# Hedgehog.net
KiCad netlist of a schematic drawn in EasyEDA Pro
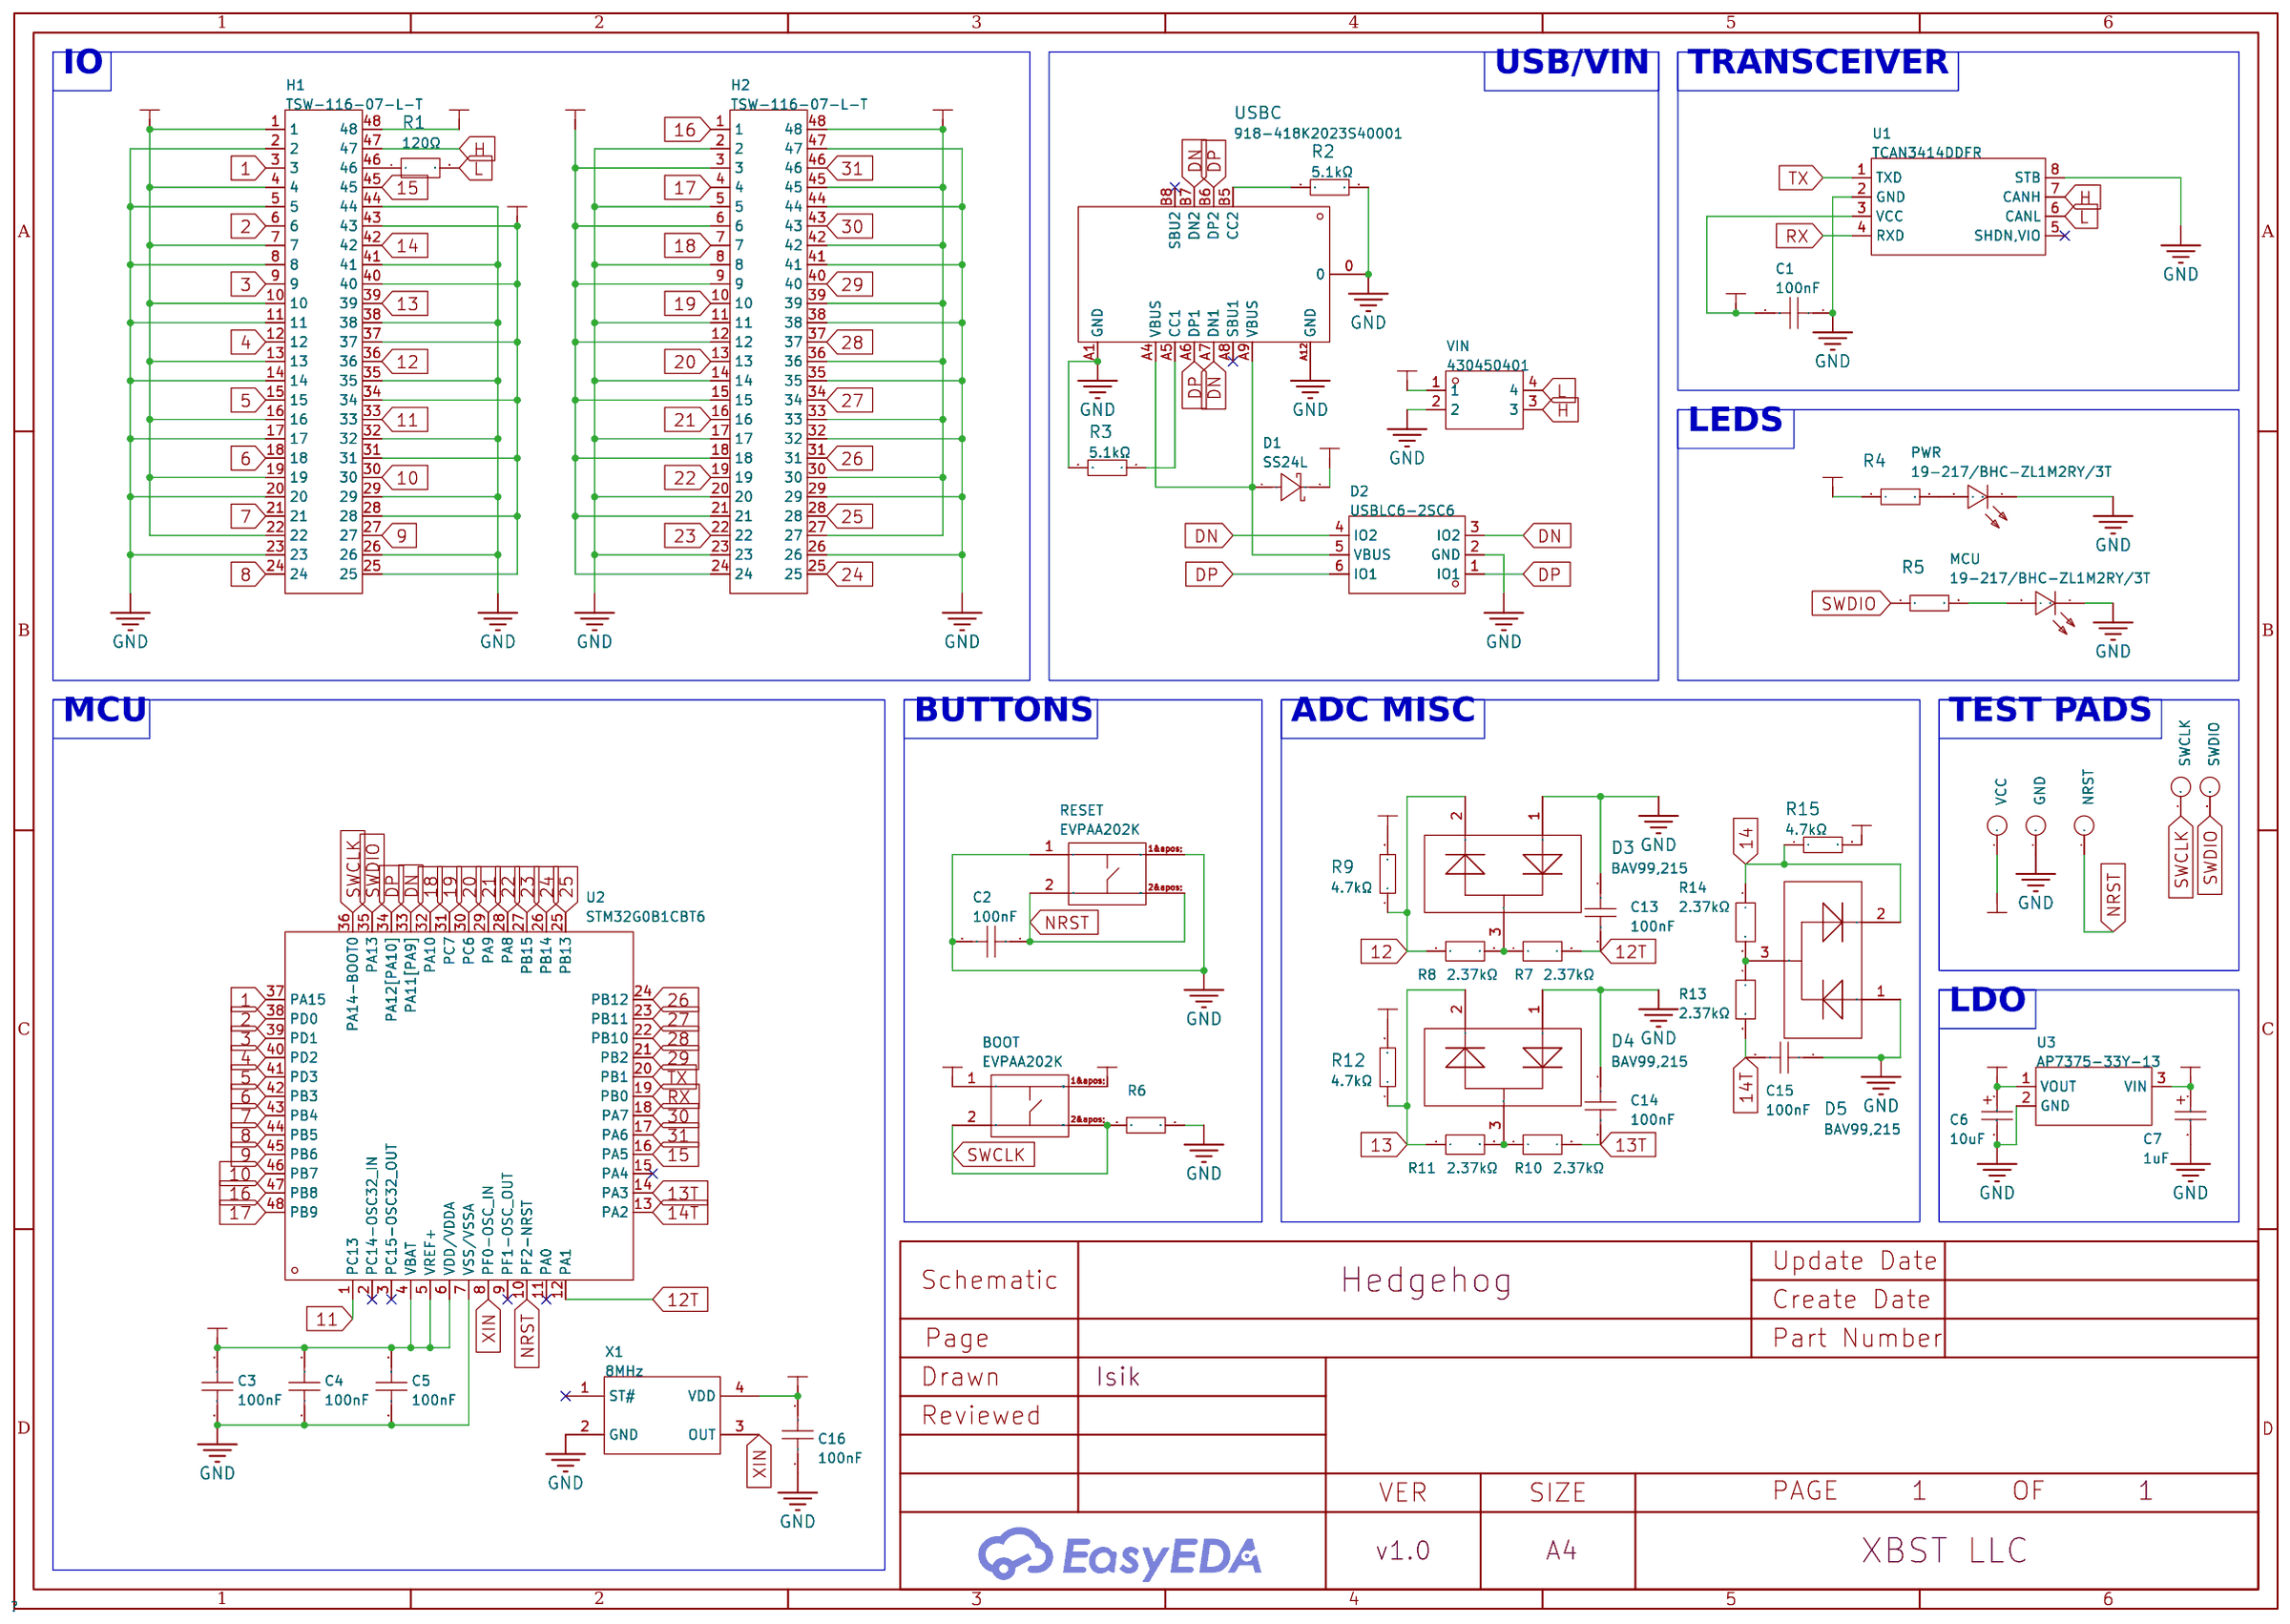
[diagram p0: schematic sheet]

(export (version "E")
  (design (tool "Eeschema 10.0.6"))
  (components
    (comp (ref "BOOT")
      (value "EVPAA202K")
      (footprint "easyedapro:KEY-SMD_4P-L3.5-W2.9-P1.48-LS4.3-TL")
      (fields (field (name "Manufacturer") "PANASONIC(松下)"))
      (libsource (lib "easyedapro") (part "EVPAA202K"))
    )
    (comp (ref "C1")
      (value "100nF")
      (footprint "easyedapro:C0402")
      (fields
        (field (name "Manufacturer Part") "CL05B104KB54PNC")
        (field (name "Manufacturer") "SAMSUNG(三星)")
      )
      (libsource (lib "easyedapro") (part "CL05B104KB54PNC"))
    )
    (comp (ref "C2")
      (value "100nF")
      (footprint "easyedapro:C0402")
      (fields
        (field (name "Manufacturer Part") "CL05B104KB54PNC")
        (field (name "Manufacturer") "SAMSUNG(三星)")
      )
      (libsource (lib "easyedapro") (part "CL05B104KB54PNC"))
    )
    (comp (ref "C3")
      (value "100nF")
      (footprint "easyedapro:C0402")
      (fields
        (field (name "Manufacturer Part") "CL05B104KB54PNC")
        (field (name "Manufacturer") "SAMSUNG(三星)")
      )
      (libsource (lib "easyedapro") (part "CL05B104KB54PNC"))
    )
    (comp (ref "C4")
      (value "100nF")
      (footprint "easyedapro:C0402")
      (fields
        (field (name "Manufacturer Part") "CL05B104KB54PNC")
        (field (name "Manufacturer") "SAMSUNG(三星)")
      )
      (libsource (lib "easyedapro") (part "CL05B104KB54PNC"))
    )
    (comp (ref "C5")
      (value "100nF")
      (footprint "easyedapro:C0402")
      (fields
        (field (name "Manufacturer Part") "CL05B104KB54PNC")
        (field (name "Manufacturer") "SAMSUNG(三星)")
      )
      (libsource (lib "easyedapro") (part "CL05B104KB54PNC"))
    )
    (comp (ref "C6")
      (value "10uF")
      (footprint "easyedapro:CAP-SMD_L3.2-W1.6-RD-C7171")
      (fields (field (name "Manufacturer Part") "TAJA106K016RNJ") (field (name "Manufacturer") "Kyocera AVX"))
      (libsource (lib "easyedapro") (part "TAJA106K016RNJ"))
    )
    (comp (ref "C7")
      (value "1uF")
      (footprint "easyedapro:CAP-SMD_L3.2-W1.6-RD-C7171")
      (fields (field (name "Manufacturer Part") "TAJA105K035RNJ") (field (name "Manufacturer") "Kyocera AVX"))
      (libsource (lib "easyedapro") (part "TAJA106K016RNJ"))
    )
    (comp (ref "C13")
      (value "100nF")
      (footprint "easyedapro:C0402")
      (fields
        (field (name "Manufacturer Part") "CL05B104KB54PNC")
        (field (name "Manufacturer") "SAMSUNG(三星)")
      )
      (libsource (lib "easyedapro") (part "CL05B104KB54PNC"))
    )
    (comp (ref "C14")
      (value "100nF")
      (footprint "easyedapro:C0402")
      (fields
        (field (name "Manufacturer Part") "CL05B104KB54PNC")
        (field (name "Manufacturer") "SAMSUNG(三星)")
      )
      (libsource (lib "easyedapro") (part "CL05B104KB54PNC"))
    )
    (comp (ref "C15")
      (value "100nF")
      (footprint "easyedapro:C0402")
      (fields
        (field (name "Manufacturer Part") "CL05B104KB54PNC")
        (field (name "Manufacturer") "SAMSUNG(三星)")
      )
      (libsource (lib "easyedapro") (part "CL05B104KB54PNC"))
    )
    (comp (ref "C16")
      (value "100nF")
      (footprint "easyedapro:C0402")
      (fields
        (field (name "Manufacturer Part") "CL05B104KB54PNC")
        (field (name "Manufacturer") "SAMSUNG(三星)")
      )
      (libsource (lib "easyedapro") (part "CL05B104KB54PNC"))
    )
    (comp (ref "D1")
      (value "SS24L")
      (footprint "easyedapro:SOD-123FL_L2.8-W1.8-LS3.7-R-RD")
      (fields (field (name "Manufacturer") "Hottech(合科泰)"))
      (libsource (lib "easyedapro") (part "SS24L"))
    )
    (comp (ref "D2")
      (value "USBLC6-2SC6")
      (footprint "easyedapro:SOT-23-6_L2.9-W1.6-P0.95-LS2.8-BL")
      (fields (field (name "Manufacturer") "TECH PUBLIC(台舟)"))
      (libsource (lib "easyedapro") (part "USBLC6-2SC6_C2827654"))
    )
    (comp (ref "D3")
      (value "BAV99,215")
      (footprint "easyedapro:SOT-23-3_L2.9-W1.6-P1.90-LS2.8-BR")
      (fields (field (name "Manufacturer") "Nexperia(安世)"))
      (libsource (lib "easyedapro") (part "BAV99,215"))
    )
    (comp (ref "D4")
      (value "BAV99,215")
      (footprint "easyedapro:SOT-23-3_L2.9-W1.6-P1.90-LS2.8-BR")
      (fields (field (name "Manufacturer") "Nexperia(安世)"))
      (libsource (lib "easyedapro") (part "BAV99,215"))
    )
    (comp (ref "D5")
      (value "BAV99,215")
      (footprint "easyedapro:SOT-23-3_L2.9-W1.6-P1.90-LS2.8-BR")
      (fields (field (name "Manufacturer") "Nexperia(安世)"))
      (libsource (lib "easyedapro") (part "BAV99,215"))
    )
    (comp (ref "GND") (value "NO") (footprint "easyedapro:TP") (libsource (lib "easyedapro") (part "NO")))
    (comp (ref "H1")
      (value "TSW-116-07-L-T")
      (footprint "easyedapro:HDR-TH_48P-P2.54-V-M-R3-C16-S2.54_1")
      (fields (field (name "Manufacturer") "SAMTEC"))
      (libsource (lib "easyedapro") (part "TSW-116-07-L-T"))
    )
    (comp (ref "H2")
      (value "TSW-116-07-L-T")
      (footprint "easyedapro:HDR-TH_48P-P2.54-V-M-R3-C16-S2.54_1")
      (fields (field (name "Manufacturer") "SAMTEC"))
      (libsource (lib "easyedapro") (part "TSW-116-07-L-T"))
    )
    (comp (ref "MCU")
      (value "19-217/BHC-ZL1M2RY/3T")
      (footprint "easyedapro:LED0603-FD_BLUE")
      (fields (field (name "Manufacturer") "EVERLIGHT(亿光)"))
      (libsource (lib "easyedapro") (part "19-217/BHC-ZL1M2RY/3T"))
    )
    (comp (ref "NRST") (value "NO") (footprint "easyedapro:TP") (libsource (lib "easyedapro") (part "NO")))
    (comp (ref "PWR")
      (value "19-217/BHC-ZL1M2RY/3T")
      (footprint "easyedapro:LED0603-FD_BLUE")
      (fields (field (name "Manufacturer") "EVERLIGHT(亿光)"))
      (libsource (lib "easyedapro") (part "19-217/BHC-ZL1M2RY/3T"))
    )
    (comp (ref "R1")
      (value "120Ω")
      (footprint "easyedapro:R0805")
      (fields (field (name "Manufacturer Part") "ERJP06F1200V") (field (name "Manufacturer") "PANASONIC(松下)"))
      (libsource (lib "easyedapro") (part "ERJP06F1200V"))
    )
    (comp (ref "R2")
      (value "5.1kΩ")
      (footprint "easyedapro:R0402")
      (fields
        (field (name "Manufacturer Part") "0402WGF5101TCE")
        (field (name "Manufacturer") "UNI-ROYAL(厚声)")
      )
      (libsource (lib "easyedapro") (part "0402WGF5101TCE"))
    )
    (comp (ref "R3")
      (value "5.1kΩ")
      (footprint "easyedapro:R0402")
      (fields
        (field (name "Manufacturer Part") "0402WGF5101TCE")
        (field (name "Manufacturer") "UNI-ROYAL(厚声)")
      )
      (libsource (lib "easyedapro") (part "0402WGF5101TCE"))
    )
    (comp (ref "R4")
      (value "1.5kΩ")
      (footprint "easyedapro:R0402")
      (fields
        (field (name "Manufacturer Part") "0402WGF1501TCE")
        (field (name "Manufacturer") "UNI-ROYAL(厚声)")
      )
      (libsource (lib "easyedapro") (part "0402WGF1501TCE"))
    )
    (comp (ref "R5")
      (value "1.5kΩ")
      (footprint "easyedapro:R0402")
      (fields
        (field (name "Manufacturer Part") "0402WGF1501TCE")
        (field (name "Manufacturer") "UNI-ROYAL(厚声)")
      )
      (libsource (lib "easyedapro") (part "0402WGF1501TCE"))
    )
    (comp (ref "R6")
      (value "10kΩ")
      (footprint "easyedapro:R0402")
      (fields
        (field (name "Manufacturer Part") "0402WGF1002TCE")
        (field (name "Manufacturer") "UNI-ROYAL(厚声)")
      )
      (libsource (lib "easyedapro") (part "0402WGF1002TCE"))
    )
    (comp (ref "R7")
      (value "2.37kΩ")
      (footprint "easyedapro:R0402")
      (fields (field (name "Manufacturer Part") "RC0402FR-072K37L") (field (name "Manufacturer") "YAGEO(国巨)"))
      (libsource (lib "easyedapro") (part "RC0402FR-072K37L_C294439"))
    )
    (comp (ref "R8")
      (value "2.37kΩ")
      (footprint "easyedapro:R0402")
      (fields (field (name "Manufacturer Part") "RC0402FR-072K37L") (field (name "Manufacturer") "YAGEO(国巨)"))
      (libsource (lib "easyedapro") (part "RC0402FR-072K37L_C294439"))
    )
    (comp (ref "R9")
      (value "4.7kΩ")
      (footprint "easyedapro:R0402")
      (fields
        (field (name "Manufacturer Part") "0402WGF4701TCE")
        (field (name "Manufacturer") "UNI-ROYAL(厚声)")
      )
      (libsource (lib "easyedapro") (part "0402WGF4701TCE"))
    )
    (comp (ref "R10")
      (value "2.37kΩ")
      (footprint "easyedapro:R0402")
      (fields (field (name "Manufacturer Part") "RC0402FR-072K37L") (field (name "Manufacturer") "YAGEO(国巨)"))
      (libsource (lib "easyedapro") (part "RC0402FR-072K37L_C294439"))
    )
    (comp (ref "R11")
      (value "2.37kΩ")
      (footprint "easyedapro:R0402")
      (fields (field (name "Manufacturer Part") "RC0402FR-072K37L") (field (name "Manufacturer") "YAGEO(国巨)"))
      (libsource (lib "easyedapro") (part "RC0402FR-072K37L_C294439"))
    )
    (comp (ref "R12")
      (value "4.7kΩ")
      (footprint "easyedapro:R0402")
      (fields
        (field (name "Manufacturer Part") "0402WGF4701TCE")
        (field (name "Manufacturer") "UNI-ROYAL(厚声)")
      )
      (libsource (lib "easyedapro") (part "0402WGF4701TCE"))
    )
    (comp (ref "R13")
      (value "2.37kΩ")
      (footprint "easyedapro:R0402")
      (fields (field (name "Manufacturer Part") "RC0402FR-072K37L") (field (name "Manufacturer") "YAGEO(国巨)"))
      (libsource (lib "easyedapro") (part "RC0402FR-072K37L_C294439"))
    )
    (comp (ref "R14")
      (value "2.37kΩ")
      (footprint "easyedapro:R0402")
      (fields (field (name "Manufacturer Part") "RC0402FR-072K37L") (field (name "Manufacturer") "YAGEO(国巨)"))
      (libsource (lib "easyedapro") (part "RC0402FR-072K37L_C294439"))
    )
    (comp (ref "R15")
      (value "4.7kΩ")
      (footprint "easyedapro:R0402")
      (fields
        (field (name "Manufacturer Part") "0402WGF4701TCE")
        (field (name "Manufacturer") "UNI-ROYAL(厚声)")
      )
      (libsource (lib "easyedapro") (part "0402WGF4701TCE"))
    )
    (comp (ref "RESET")
      (value "EVPAA202K")
      (footprint "easyedapro:KEY-SMD_4P-L3.5-W2.9-P1.48-LS4.3-TL")
      (fields (field (name "Manufacturer") "PANASONIC(松下)"))
      (libsource (lib "easyedapro") (part "EVPAA202K"))
    )
    (comp (ref "SWCLK") (value "NO") (footprint "easyedapro:TP") (libsource (lib "easyedapro") (part "NO")))
    (comp (ref "SWDIO") (value "NO") (footprint "easyedapro:TP") (libsource (lib "easyedapro") (part "NO")))
    (comp (ref "U1")
      (value "TCAN3414DDFR")
      (footprint "easyedapro:TSOT-23-8_L2.9-W1.6-P0.65-LS2.8-BR")
      (fields (field (name "Manufacturer") "TI(德州仪器)"))
      (libsource (lib "easyedapro") (part "TCAN3414DDFR"))
    )
    (comp (ref "U2")
      (value "STM32G0B1CBT6")
      (footprint "easyedapro:LQFP-48_L7.0-W7.0-P0.50-LS9.0-BL")
      (fields (field (name "Manufacturer") "ST(意法半导体)"))
      (libsource (lib "easyedapro") (part "STM32G0B1CBT6"))
    )
    (comp (ref "U3")
      (value "AP7375-33Y-13")
      (footprint "easyedapro:SOT-89-3_L4.5-W2.5-P1.50-LS4.0-BR")
      (fields (field (name "Manufacturer") "DIODES(美台)"))
      (libsource (lib "easyedapro") (part "AP7375-33Y-13"))
    )
    (comp (ref "USBC")
      (value "918-418K2023S40001")
      (footprint "easyedapro:USB-C-SMD_TYPE-C-USB-17")
      (fields (field (name "Manufacturer") "精拓金"))
      (libsource (lib "easyedapro") (part "USB3.1C16PFSMT"))
    )
    (comp (ref "VCC") (value "NO") (footprint "easyedapro:TP") (libsource (lib "easyedapro") (part "NO")))
    (comp (ref "VIN")
      (value "430450401")
      (footprint "easyedapro:CONN-TH_0430450400")
      (fields (field (name "Manufacturer") "MOLEX"))
      (libsource (lib "easyedapro") (part "430450401"))
    )
    (comp (ref "X1")
      (value "8MHz")
      (footprint "easyedapro:OSC-SMD_4P-L2.5-W2.0-BL")
      (fields (field (name "Manufacturer Part") "SG-210STF 8.0000ML0") (field (name "Manufacturer") "EPSON"))
      (libsource (lib "easyedapro") (part "X1G004171003300"))
    )
  )
  (nets
    (net (code "1") (name "1") (class "Default")
      (node (ref "H1") (pin "3") (pinfunction "3_3") (pintype "unspecified"))
      (node (ref "U2") (pin "37") (pinfunction "PA15_37") (pintype "unspecified"))
    )
    (net (code "2") (name "2") (class "Default")
      (node (ref "H1") (pin "6") (pinfunction "6_6") (pintype "unspecified"))
      (node (ref "U2") (pin "38") (pinfunction "PD0_38") (pintype "unspecified"))
    )
    (net (code "3") (name "3") (class "Default")
      (node (ref "H1") (pin "9") (pinfunction "9_9") (pintype "unspecified"))
      (node (ref "U2") (pin "39") (pinfunction "PD1_39") (pintype "unspecified"))
    )
    (net (code "4") (name "3V3") (class "Default")
      (node (ref "BOOT") (pin "1") (pinfunction "1_1") (pintype "unspecified"))
      (node (ref "BOOT") (pin "1&apos;") (pinfunction "1&apos;_1&apos;") (pintype "unspecified"))
      (node (ref "C1") (pin "2") (pinfunction "2_2") (pintype "input"))
      (node (ref "C16") (pin "2") (pinfunction "2_2") (pintype "input"))
      (node (ref "C3") (pin "1") (pinfunction "1_1") (pintype "input"))
      (node (ref "C4") (pin "2") (pinfunction "2_2") (pintype "input"))
      (node (ref "C5") (pin "2") (pinfunction "2_2") (pintype "input"))
      (node (ref "C6") (pin "1") (pinfunction "1_1") (pintype "input"))
      (node (ref "H1") (pin "1") (pinfunction "1_1") (pintype "unspecified"))
      (node (ref "H1") (pin "10") (pinfunction "10_10") (pintype "unspecified"))
      (node (ref "H1") (pin "13") (pinfunction "13_13") (pintype "unspecified"))
      (node (ref "H1") (pin "16") (pinfunction "16_16") (pintype "unspecified"))
      (node (ref "H1") (pin "19") (pinfunction "19_19") (pintype "unspecified"))
      (node (ref "H1") (pin "22") (pinfunction "22_22") (pintype "unspecified"))
      (node (ref "H1") (pin "25") (pinfunction "25_25") (pintype "unspecified"))
      (node (ref "H1") (pin "28") (pinfunction "28_28") (pintype "unspecified"))
      (node (ref "H1") (pin "31") (pinfunction "31_31") (pintype "unspecified"))
      (node (ref "H1") (pin "34") (pinfunction "34_34") (pintype "unspecified"))
      (node (ref "H1") (pin "37") (pinfunction "37_37") (pintype "unspecified"))
      (node (ref "H1") (pin "4") (pinfunction "4_4") (pintype "unspecified"))
      (node (ref "H1") (pin "40") (pinfunction "40_40") (pintype "unspecified"))
      (node (ref "H1") (pin "43") (pinfunction "43_43") (pintype "unspecified"))
      (node (ref "H1") (pin "7") (pinfunction "7_7") (pintype "unspecified"))
      (node (ref "H2") (pin "12") (pinfunction "12_12") (pintype "unspecified"))
      (node (ref "H2") (pin "15") (pinfunction "15_15") (pintype "unspecified"))
      (node (ref "H2") (pin "18") (pinfunction "18_18") (pintype "unspecified"))
      (node (ref "H2") (pin "21") (pinfunction "21_21") (pintype "unspecified"))
      (node (ref "H2") (pin "24") (pinfunction "24_24") (pintype "unspecified"))
      (node (ref "H2") (pin "27") (pinfunction "27_27") (pintype "unspecified"))
      (node (ref "H2") (pin "3") (pinfunction "3_3") (pintype "unspecified"))
      (node (ref "H2") (pin "30") (pinfunction "30_30") (pintype "unspecified"))
      (node (ref "H2") (pin "33") (pinfunction "33_33") (pintype "unspecified"))
      (node (ref "H2") (pin "36") (pinfunction "36_36") (pintype "unspecified"))
      (node (ref "H2") (pin "39") (pinfunction "39_39") (pintype "unspecified"))
      (node (ref "H2") (pin "42") (pinfunction "42_42") (pintype "unspecified"))
      (node (ref "H2") (pin "45") (pinfunction "45_45") (pintype "unspecified"))
      (node (ref "H2") (pin "48") (pinfunction "48_48") (pintype "unspecified"))
      (node (ref "H2") (pin "6") (pinfunction "6_6") (pintype "unspecified"))
      (node (ref "H2") (pin "9") (pinfunction "9_9") (pintype "unspecified"))
      (node (ref "R12") (pin "2") (pinfunction "2_2") (pintype "input"))
      (node (ref "R15") (pin "2") (pinfunction "2_2") (pintype "input"))
      (node (ref "R4") (pin "1") (pinfunction "1_1") (pintype "input"))
      (node (ref "R9") (pin "2") (pinfunction "2_2") (pintype "input"))
      (node (ref "U1") (pin "3") (pinfunction "VCC_3") (pintype "unspecified"))
      (node (ref "U2") (pin "4") (pinfunction "VBAT_4") (pintype "unspecified"))
      (node (ref "U2") (pin "5") (pinfunction "VREF+_5") (pintype "unspecified"))
      (node (ref "U2") (pin "6") (pinfunction "VDD/VDDA_6") (pintype "unspecified"))
      (node (ref "U3") (pin "1") (pinfunction "VOUT_1") (pintype "unspecified"))
      (node (ref "VCC") (pin "1") (pinfunction "1_1") (pintype "unspecified"))
      (node (ref "X1") (pin "4") (pinfunction "VDD_4") (pintype "unspecified"))
    )
    (net (code "5") (name "4") (class "Default")
      (node (ref "H1") (pin "12") (pinfunction "12_12") (pintype "unspecified"))
      (node (ref "U2") (pin "40") (pinfunction "PD2_40") (pintype "unspecified"))
    )
    (net (code "6") (name "5") (class "Default")
      (node (ref "H1") (pin "15") (pinfunction "15_15") (pintype "unspecified"))
      (node (ref "U2") (pin "41") (pinfunction "PD3_41") (pintype "unspecified"))
    )
    (net (code "7") (name "6") (class "Default")
      (node (ref "H1") (pin "18") (pinfunction "18_18") (pintype "unspecified"))
      (node (ref "U2") (pin "42") (pinfunction "PB3_42") (pintype "unspecified"))
    )
    (net (code "8") (name "7") (class "Default")
      (node (ref "H1") (pin "21") (pinfunction "21_21") (pintype "unspecified"))
      (node (ref "U2") (pin "43") (pinfunction "PB4_43") (pintype "unspecified"))
    )
    (net (code "9") (name "8") (class "Default")
      (node (ref "H1") (pin "24") (pinfunction "24_24") (pintype "unspecified"))
      (node (ref "U2") (pin "44") (pinfunction "PB5_44") (pintype "unspecified"))
    )
    (net (code "10") (name "9") (class "Default")
      (node (ref "H1") (pin "27") (pinfunction "27_27") (pintype "unspecified"))
      (node (ref "U2") (pin "45") (pinfunction "PB6_45") (pintype "unspecified"))
    )
    (net (code "11") (name "10") (class "Default")
      (node (ref "H1") (pin "30") (pinfunction "30_30") (pintype "unspecified"))
      (node (ref "U2") (pin "46") (pinfunction "PB7_46") (pintype "unspecified"))
    )
    (net (code "12") (name "11") (class "Default")
      (node (ref "H1") (pin "33") (pinfunction "33_33") (pintype "unspecified"))
      (node (ref "U2") (pin "1") (pinfunction "PC13_1") (pintype "unspecified"))
    )
    (net (code "13") (name "12") (class "Default")
      (node (ref "D3") (pin "2") (pinfunction "2_2") (pintype "input"))
      (node (ref "H1") (pin "36") (pinfunction "36_36") (pintype "unspecified"))
      (node (ref "R8") (pin "1") (pinfunction "1_1") (pintype "input"))
      (node (ref "R9") (pin "1") (pinfunction "1_1") (pintype "input"))
    )
    (net (code "14") (name "12T") (class "Default")
      (node (ref "C13") (pin "2") (pinfunction "2_2") (pintype "input"))
      (node (ref "R7") (pin "2") (pinfunction "2_2") (pintype "input"))
      (node (ref "U2") (pin "12") (pinfunction "PA1_12") (pintype "unspecified"))
    )
    (net (code "15") (name "13") (class "Default")
      (node (ref "D4") (pin "2") (pinfunction "2_2") (pintype "input"))
      (node (ref "H1") (pin "39") (pinfunction "39_39") (pintype "unspecified"))
      (node (ref "R11") (pin "1") (pinfunction "1_1") (pintype "input"))
      (node (ref "R12") (pin "1") (pinfunction "1_1") (pintype "input"))
    )
    (net (code "16") (name "13T") (class "Default")
      (node (ref "C14") (pin "2") (pinfunction "2_2") (pintype "input"))
      (node (ref "R10") (pin "2") (pinfunction "2_2") (pintype "input"))
      (node (ref "U2") (pin "14") (pinfunction "PA3_14") (pintype "unspecified"))
    )
    (net (code "17") (name "14") (class "Default")
      (node (ref "D5") (pin "2") (pinfunction "2_2") (pintype "input"))
      (node (ref "H1") (pin "42") (pinfunction "42_42") (pintype "unspecified"))
      (node (ref "R14") (pin "1") (pinfunction "1_1") (pintype "input"))
      (node (ref "R15") (pin "1") (pinfunction "1_1") (pintype "input"))
    )
    (net (code "18") (name "14T") (class "Default")
      (node (ref "C15") (pin "2") (pinfunction "2_2") (pintype "input"))
      (node (ref "R13") (pin "2") (pinfunction "2_2") (pintype "input"))
      (node (ref "U2") (pin "13") (pinfunction "PA2_13") (pintype "unspecified"))
    )
    (net (code "19") (name "15") (class "Default")
      (node (ref "H1") (pin "45") (pinfunction "45_45") (pintype "unspecified"))
      (node (ref "U2") (pin "16") (pinfunction "PA5_16") (pintype "unspecified"))
    )
    (net (code "20") (name "16") (class "Default")
      (node (ref "H2") (pin "1") (pinfunction "1_1") (pintype "unspecified"))
      (node (ref "U2") (pin "47") (pinfunction "PB8_47") (pintype "unspecified"))
    )
    (net (code "21") (name "17") (class "Default")
      (node (ref "H2") (pin "4") (pinfunction "4_4") (pintype "unspecified"))
      (node (ref "U2") (pin "48") (pinfunction "PB9_48") (pintype "unspecified"))
    )
    (net (code "22") (name "18") (class "Default")
      (node (ref "H2") (pin "7") (pinfunction "7_7") (pintype "unspecified"))
      (node (ref "U2") (pin "32") (pinfunction "PA10_32") (pintype "unspecified"))
    )
    (net (code "23") (name "19") (class "Default")
      (node (ref "H2") (pin "10") (pinfunction "10_10") (pintype "unspecified"))
      (node (ref "U2") (pin "31") (pinfunction "PC7_31") (pintype "unspecified"))
    )
    (net (code "24") (name "20") (class "Default")
      (node (ref "H2") (pin "13") (pinfunction "13_13") (pintype "unspecified"))
      (node (ref "U2") (pin "30") (pinfunction "PC6_30") (pintype "unspecified"))
    )
    (net (code "25") (name "21") (class "Default")
      (node (ref "H2") (pin "16") (pinfunction "16_16") (pintype "unspecified"))
      (node (ref "U2") (pin "29") (pinfunction "PA9_29") (pintype "unspecified"))
    )
    (net (code "26") (name "22") (class "Default")
      (node (ref "H2") (pin "19") (pinfunction "19_19") (pintype "unspecified"))
      (node (ref "U2") (pin "28") (pinfunction "PA8_28") (pintype "unspecified"))
    )
    (net (code "27") (name "23") (class "Default")
      (node (ref "H2") (pin "22") (pinfunction "22_22") (pintype "unspecified"))
      (node (ref "U2") (pin "27") (pinfunction "PB15_27") (pintype "unspecified"))
    )
    (net (code "28") (name "24") (class "Default")
      (node (ref "H2") (pin "25") (pinfunction "25_25") (pintype "unspecified"))
      (node (ref "U2") (pin "26") (pinfunction "PB14_26") (pintype "unspecified"))
    )
    (net (code "29") (name "25") (class "Default")
      (node (ref "H2") (pin "28") (pinfunction "28_28") (pintype "unspecified"))
      (node (ref "U2") (pin "25") (pinfunction "PB13_25") (pintype "unspecified"))
    )
    (net (code "30") (name "26") (class "Default")
      (node (ref "H2") (pin "31") (pinfunction "31_31") (pintype "unspecified"))
      (node (ref "U2") (pin "24") (pinfunction "PB12_24") (pintype "unspecified"))
    )
    (net (code "31") (name "27") (class "Default")
      (node (ref "H2") (pin "34") (pinfunction "34_34") (pintype "unspecified"))
      (node (ref "U2") (pin "23") (pinfunction "PB11_23") (pintype "unspecified"))
    )
    (net (code "32") (name "28") (class "Default")
      (node (ref "H2") (pin "37") (pinfunction "37_37") (pintype "unspecified"))
      (node (ref "U2") (pin "22") (pinfunction "PB10_22") (pintype "unspecified"))
    )
    (net (code "33") (name "29") (class "Default")
      (node (ref "H2") (pin "40") (pinfunction "40_40") (pintype "unspecified"))
      (node (ref "U2") (pin "21") (pinfunction "PB2_21") (pintype "unspecified"))
    )
    (net (code "34") (name "30") (class "Default")
      (node (ref "H2") (pin "43") (pinfunction "43_43") (pintype "unspecified"))
      (node (ref "U2") (pin "18") (pinfunction "PA7_18") (pintype "unspecified"))
    )
    (net (code "35") (name "31") (class "Default")
      (node (ref "H2") (pin "46") (pinfunction "46_46") (pintype "unspecified"))
      (node (ref "U2") (pin "17") (pinfunction "PA6_17") (pintype "unspecified"))
    )
    (net (code "36") (name "DN") (class "Default")
      (node (ref "D2") (pin "3") (pinfunction "IO2_3") (pintype "unspecified"))
      (node (ref "D2") (pin "4") (pinfunction "IO2_4") (pintype "unspecified"))
      (node (ref "U2") (pin "33") (pinfunction "PA11[PA9]_33") (pintype "unspecified"))
      (node (ref "USBC") (pin "A7") (pinfunction "DN1_A7") (pintype "input"))
      (node (ref "USBC") (pin "B7") (pinfunction "DN2_B7") (pintype "input"))
    )
    (net (code "37") (name "DP") (class "Default")
      (node (ref "D2") (pin "1") (pinfunction "IO1_1") (pintype "unspecified"))
      (node (ref "D2") (pin "6") (pinfunction "IO1_6") (pintype "unspecified"))
      (node (ref "U2") (pin "34") (pinfunction "PA12[PA10]_34") (pintype "unspecified"))
      (node (ref "USBC") (pin "A6") (pinfunction "DP1_A6") (pintype "input"))
      (node (ref "USBC") (pin "B6") (pinfunction "DP2_B6") (pintype "input"))
    )
    (net (code "38") (name "GND") (class "Default")
      (node (ref "C1") (pin "1") (pinfunction "1_1") (pintype "input"))
      (node (ref "C13") (pin "1") (pinfunction "1_1") (pintype "input"))
      (node (ref "C14") (pin "1") (pinfunction "1_1") (pintype "input"))
      (node (ref "C15") (pin "1") (pinfunction "1_1") (pintype "input"))
      (node (ref "C16") (pin "1") (pinfunction "1_1") (pintype "input"))
      (node (ref "C2") (pin "2") (pinfunction "2_2") (pintype "input"))
      (node (ref "C3") (pin "2") (pinfunction "2_2") (pintype "input"))
      (node (ref "C4") (pin "1") (pinfunction "1_1") (pintype "input"))
      (node (ref "C5") (pin "1") (pinfunction "1_1") (pintype "input"))
      (node (ref "C6") (pin "2") (pinfunction "2_2") (pintype "input"))
      (node (ref "C7") (pin "2") (pinfunction "2_2") (pintype "input"))
      (node (ref "D2") (pin "2") (pinfunction "GND_2") (pintype "unspecified"))
      (node (ref "D3") (pin "1") (pinfunction "1_1") (pintype "input"))
      (node (ref "D4") (pin "1") (pinfunction "1_1") (pintype "input"))
      (node (ref "D5") (pin "1") (pinfunction "1_1") (pintype "input"))
      (node (ref "GND") (pin "1") (pinfunction "1_1") (pintype "unspecified"))
      (node (ref "H1") (pin "11") (pinfunction "11_11") (pintype "unspecified"))
      (node (ref "H1") (pin "14") (pinfunction "14_14") (pintype "unspecified"))
      (node (ref "H1") (pin "17") (pinfunction "17_17") (pintype "unspecified"))
      (node (ref "H1") (pin "2") (pinfunction "2_2") (pintype "unspecified"))
      (node (ref "H1") (pin "20") (pinfunction "20_20") (pintype "unspecified"))
      (node (ref "H1") (pin "23") (pinfunction "23_23") (pintype "unspecified"))
      (node (ref "H1") (pin "26") (pinfunction "26_26") (pintype "unspecified"))
      (node (ref "H1") (pin "29") (pinfunction "29_29") (pintype "unspecified"))
      (node (ref "H1") (pin "32") (pinfunction "32_32") (pintype "unspecified"))
      (node (ref "H1") (pin "35") (pinfunction "35_35") (pintype "unspecified"))
      (node (ref "H1") (pin "38") (pinfunction "38_38") (pintype "unspecified"))
      (node (ref "H1") (pin "41") (pinfunction "41_41") (pintype "unspecified"))
      (node (ref "H1") (pin "44") (pinfunction "44_44") (pintype "unspecified"))
      (node (ref "H1") (pin "5") (pinfunction "5_5") (pintype "unspecified"))
      (node (ref "H1") (pin "8") (pinfunction "8_8") (pintype "unspecified"))
      (node (ref "H2") (pin "11") (pinfunction "11_11") (pintype "unspecified"))
      (node (ref "H2") (pin "14") (pinfunction "14_14") (pintype "unspecified"))
      (node (ref "H2") (pin "17") (pinfunction "17_17") (pintype "unspecified"))
      (node (ref "H2") (pin "2") (pinfunction "2_2") (pintype "unspecified"))
      (node (ref "H2") (pin "20") (pinfunction "20_20") (pintype "unspecified"))
      (node (ref "H2") (pin "23") (pinfunction "23_23") (pintype "unspecified"))
      (node (ref "H2") (pin "26") (pinfunction "26_26") (pintype "unspecified"))
      (node (ref "H2") (pin "29") (pinfunction "29_29") (pintype "unspecified"))
      (node (ref "H2") (pin "32") (pinfunction "32_32") (pintype "unspecified"))
      (node (ref "H2") (pin "35") (pinfunction "35_35") (pintype "unspecified"))
      (node (ref "H2") (pin "38") (pinfunction "38_38") (pintype "unspecified"))
      (node (ref "H2") (pin "41") (pinfunction "41_41") (pintype "unspecified"))
      (node (ref "H2") (pin "44") (pinfunction "44_44") (pintype "unspecified"))
      (node (ref "H2") (pin "47") (pinfunction "47_47") (pintype "unspecified"))
      (node (ref "H2") (pin "5") (pinfunction "5_5") (pintype "unspecified"))
      (node (ref "H2") (pin "8") (pinfunction "8_8") (pintype "unspecified"))
      (node (ref "MCU") (pin "1") (pinfunction "C_1") (pintype "input"))
      (node (ref "PWR") (pin "1") (pinfunction "C_1") (pintype "input"))
      (node (ref "R2") (pin "1") (pinfunction "1_1") (pintype "input"))
      (node (ref "R3") (pin "2") (pinfunction "2_2") (pintype "input"))
      (node (ref "R6") (pin "2") (pinfunction "2_2") (pintype "input"))
      (node (ref "RESET") (pin "1") (pinfunction "1_1") (pintype "unspecified"))
      (node (ref "RESET") (pin "1&apos;") (pinfunction "1&apos;_1&apos;") (pintype "unspecified"))
      (node (ref "U1") (pin "2") (pinfunction "GND_2") (pintype "unspecified"))
      (node (ref "U1") (pin "8") (pinfunction "STB_8") (pintype "unspecified"))
      (node (ref "U2") (pin "7") (pinfunction "VSS/VSSA_7") (pintype "unspecified"))
      (node (ref "U3") (pin "2") (pinfunction "GND_2") (pintype "unspecified"))
      (node (ref "USBC") (pin "0") (pinfunction "0_0") (pintype "input"))
      (node (ref "USBC") (pin "A1") (pinfunction "GND_A1") (pintype "input"))
      (node (ref "USBC") (pin "A12") (pinfunction "GND_A12") (pintype "input"))
      (node (ref "VIN") (pin "2") (pinfunction "2_2") (pintype "unspecified"))
      (node (ref "X1") (pin "2") (pinfunction "GND_2") (pintype "unspecified"))
    )
    (net (code "39") (name "H") (class "Default")
      (node (ref "H1") (pin "47") (pinfunction "47_47") (pintype "unspecified"))
      (node (ref "U1") (pin "7") (pinfunction "CANH_7") (pintype "unspecified"))
      (node (ref "VIN") (pin "3") (pinfunction "3_3") (pintype "unspecified"))
    )
    (net (code "40") (name "L") (class "Default")
      (node (ref "R1") (pin "2") (pinfunction "2_2") (pintype "input"))
      (node (ref "U1") (pin "6") (pinfunction "CANL_6") (pintype "unspecified"))
      (node (ref "VIN") (pin "4") (pinfunction "4_4") (pintype "unspecified"))
    )
    (net (code "41") (name "NRST") (class "Default")
      (node (ref "C2") (pin "1") (pinfunction "1_1") (pintype "input"))
      (node (ref "NRST") (pin "1") (pinfunction "1_1") (pintype "unspecified"))
      (node (ref "RESET") (pin "2") (pinfunction "2_2") (pintype "unspecified"))
      (node (ref "RESET") (pin "2&apos;") (pinfunction "2&apos;_2&apos;") (pintype "unspecified"))
      (node (ref "U2") (pin "10") (pinfunction "PF2-NRST_10") (pintype "unspecified"))
    )
    (net (code "42") (name "Net-(D1-A)") (class "Default")
      (node (ref "D1") (pin "1") (pinfunction "A_1") (pintype "unspecified"))
      (node (ref "D2") (pin "5") (pinfunction "VBUS_5") (pintype "unspecified"))
      (node (ref "USBC") (pin "A4") (pinfunction "VBUS_A4") (pintype "input"))
      (node (ref "USBC") (pin "A9") (pinfunction "VBUS_A9") (pintype "input"))
    )
    (net (code "43") (name "Net-(D3-Pad3)") (class "Default")
      (node (ref "D3") (pin "3") (pinfunction "3_3") (pintype "input"))
      (node (ref "R7") (pin "1") (pinfunction "1_1") (pintype "input"))
      (node (ref "R8") (pin "2") (pinfunction "2_2") (pintype "input"))
    )
    (net (code "44") (name "Net-(D4-Pad3)") (class "Default")
      (node (ref "D4") (pin "3") (pinfunction "3_3") (pintype "input"))
      (node (ref "R10") (pin "1") (pinfunction "1_1") (pintype "input"))
      (node (ref "R11") (pin "2") (pinfunction "2_2") (pintype "input"))
    )
    (net (code "45") (name "Net-(D5-Pad3)") (class "Default")
      (node (ref "D5") (pin "3") (pinfunction "3_3") (pintype "input"))
      (node (ref "R13") (pin "1") (pinfunction "1_1") (pintype "input"))
      (node (ref "R14") (pin "2") (pinfunction "2_2") (pintype "input"))
    )
    (net (code "46") (name "Net-(H1-Pad46)") (class "Default")
      (node (ref "H1") (pin "46") (pinfunction "46_46") (pintype "unspecified"))
      (node (ref "R1") (pin "1") (pinfunction "1_1") (pintype "input"))
    )
    (net (code "47") (name "Net-(MCU-A)") (class "Default")
      (node (ref "MCU") (pin "2") (pinfunction "A_2") (pintype "input"))
      (node (ref "R5") (pin "2") (pinfunction "2_2") (pintype "input"))
    )
    (net (code "48") (name "Net-(PWR-A)") (class "Default")
      (node (ref "PWR") (pin "2") (pinfunction "A_2") (pintype "input"))
      (node (ref "R4") (pin "2") (pinfunction "2_2") (pintype "input"))
    )
    (net (code "49") (name "Net-(USBC-CC1)") (class "Default")
      (node (ref "R3") (pin "1") (pinfunction "1_1") (pintype "input"))
      (node (ref "USBC") (pin "A5") (pinfunction "CC1_A5") (pintype "input"))
    )
    (net (code "50") (name "Net-(USBC-CC2)") (class "Default")
      (node (ref "R2") (pin "2") (pinfunction "2_2") (pintype "input"))
      (node (ref "USBC") (pin "B5") (pinfunction "CC2_B5") (pintype "input"))
    )
    (net (code "51") (name "RX") (class "Default")
      (node (ref "U1") (pin "4") (pinfunction "RXD_4") (pintype "unspecified"))
      (node (ref "U2") (pin "19") (pinfunction "PB0_19") (pintype "unspecified"))
    )
    (net (code "52") (name "SWCLK") (class "Default")
      (node (ref "BOOT") (pin "2") (pinfunction "2_2") (pintype "unspecified"))
      (node (ref "BOOT") (pin "2&apos;") (pinfunction "2&apos;_2&apos;") (pintype "unspecified"))
      (node (ref "R6") (pin "1") (pinfunction "1_1") (pintype "input"))
      (node (ref "SWCLK") (pin "1") (pinfunction "1_1") (pintype "unspecified"))
      (node (ref "U2") (pin "36") (pinfunction "PA14-BOOT0_36") (pintype "unspecified"))
    )
    (net (code "53") (name "SWDIO") (class "Default")
      (node (ref "R5") (pin "1") (pinfunction "1_1") (pintype "input"))
      (node (ref "SWDIO") (pin "1") (pinfunction "1_1") (pintype "unspecified"))
      (node (ref "U2") (pin "35") (pinfunction "PA13_35") (pintype "unspecified"))
    )
    (net (code "54") (name "TX") (class "Default")
      (node (ref "U1") (pin "1") (pinfunction "TXD_1") (pintype "unspecified"))
      (node (ref "U2") (pin "20") (pinfunction "PB1_20") (pintype "unspecified"))
    )
    (net (code "55") (name "VIN") (class "Default")
      (node (ref "C7") (pin "1") (pinfunction "1_1") (pintype "input"))
      (node (ref "D1") (pin "2") (pinfunction "K_2") (pintype "unspecified"))
      (node (ref "H1") (pin "48") (pinfunction "48_48") (pintype "unspecified"))
      (node (ref "U3") (pin "3") (pinfunction "VIN_3") (pintype "unspecified"))
      (node (ref "VIN") (pin "1") (pinfunction "1_1") (pintype "unspecified"))
    )
    (net (code "56") (name "XIN") (class "Default")
      (node (ref "U2") (pin "8") (pinfunction "PF0-OSC_IN_8") (pintype "unspecified"))
      (node (ref "X1") (pin "3") (pinfunction "OUT_3") (pintype "unspecified"))
    )
    (net (code "57") (name "unconnected-(U1-SHDN,VIO-Pad5)") (class "Default")
      (node (ref "U1") (pin "5") (pinfunction "SHDN,VIO_5") (pintype "unspecified+no_connect"))
    )
    (net (code "58") (name "unconnected-(U2-PA0-Pad11)") (class "Default")
      (node (ref "U2") (pin "11") (pinfunction "PA0_11") (pintype "unspecified+no_connect"))
    )
    (net (code "59") (name "unconnected-(U2-PA4-Pad15)") (class "Default")
      (node (ref "U2") (pin "15") (pinfunction "PA4_15") (pintype "unspecified+no_connect"))
    )
    (net (code "60") (name "unconnected-(U2-PC14-OSC32_IN-Pad2)") (class "Default")
      (node (ref "U2") (pin "2") (pinfunction "PC14-OSC32_IN_2") (pintype "unspecified+no_connect"))
    )
    (net (code "61") (name "unconnected-(U2-PC15-OSC32_OUT-Pad3)") (class "Default")
      (node (ref "U2") (pin "3") (pinfunction "PC15-OSC32_OUT_3") (pintype "unspecified+no_connect"))
    )
    (net (code "62") (name "unconnected-(U2-PF1-OSC_OUT-Pad9)") (class "Default")
      (node (ref "U2") (pin "9") (pinfunction "PF1-OSC_OUT_9") (pintype "unspecified+no_connect"))
    )
    (net (code "63") (name "unconnected-(USBC-SBU1-PadA8)") (class "Default")
      (node (ref "USBC") (pin "A8") (pinfunction "SBU1_A8") (pintype "input+no_connect"))
    )
    (net (code "64") (name "unconnected-(USBC-SBU2-PadB8)") (class "Default")
      (node (ref "USBC") (pin "B8") (pinfunction "SBU2_B8") (pintype "input+no_connect"))
    )
    (net (code "65") (name "unconnected-(X1-ST#-Pad1)") (class "Default")
      (node (ref "X1") (pin "1") (pinfunction "ST#_1") (pintype "unspecified+no_connect"))
    )
  )
)
